# S11_LEDs.net
KiCad netlist of a schematic drawn in Altium Designer
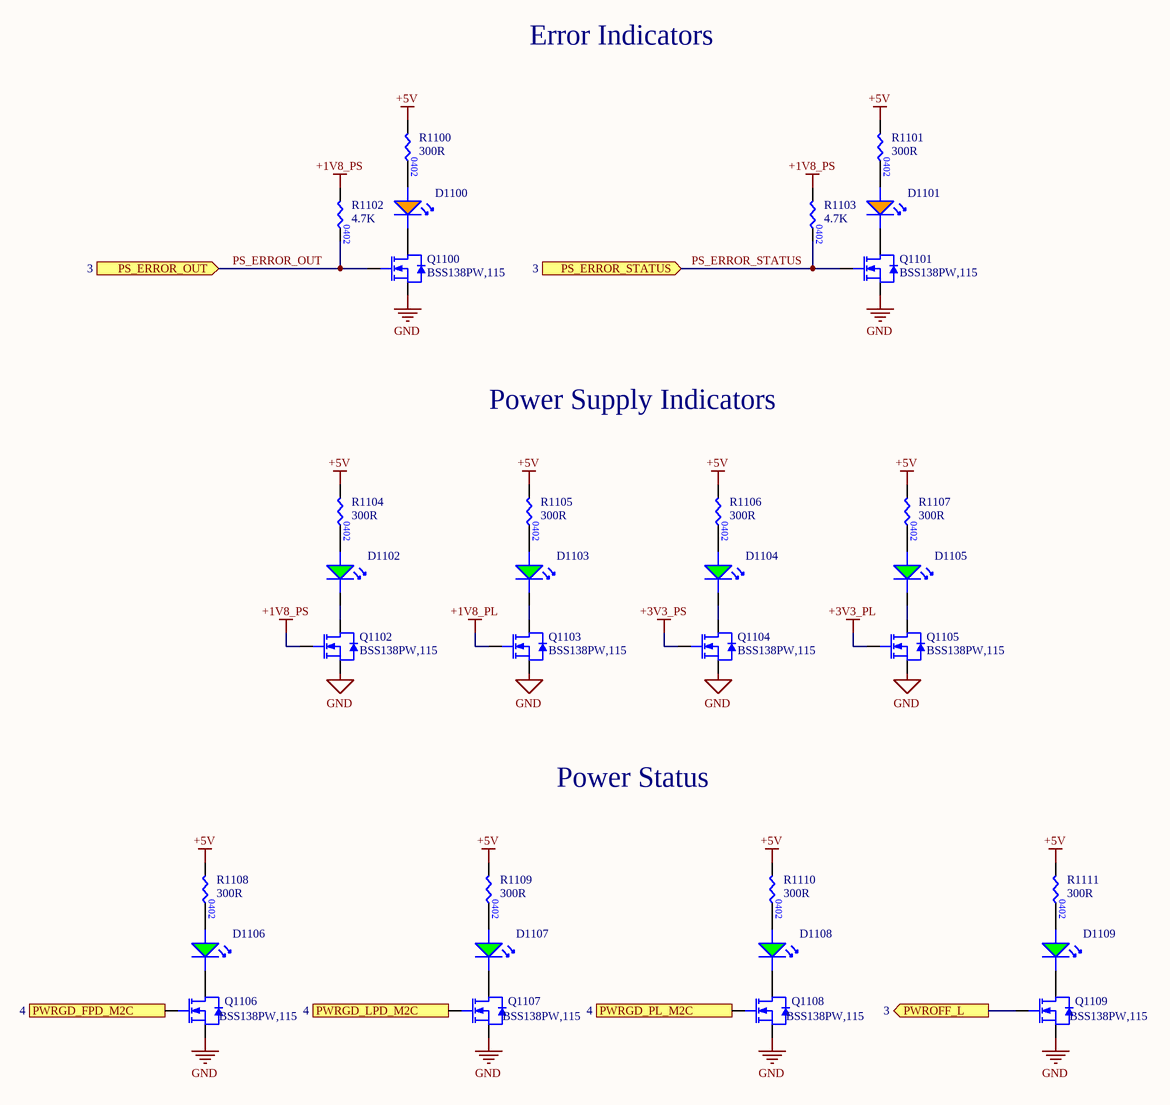
[diagram p0: S11_LEDs.SchDoc]

(export (version "E")
  (design (tool "Eeschema 10.0.6"))
  (components
    (comp (ref "D1100")
      (value "GENERIC LED - ORANGE")
      (footprint "LED_0603")
      (fields (field (name "MANUFACTURER PART NUMBER") "150060AS75000"))
      (libsource (lib "OpenCore_Sch_Lib") (part ".LED_ORANGE"))
    )
    (comp (ref "D1101")
      (value "GENERIC LED - ORANGE")
      (footprint "LED_0603")
      (fields (field (name "MANUFACTURER PART NUMBER") "150060AS75000"))
      (libsource (lib "OpenCore_Sch_Lib") (part ".LED_ORANGE"))
    )
    (comp (ref "D1102")
      (value "GENERIC LED - GREEN")
      (footprint "LED_0603")
      (fields (field (name "MANUFACTURER PART NUMBER") "150060VS75000"))
      (libsource (lib "OpenCore_Sch_Lib") (part ".LED_GREEN"))
    )
    (comp (ref "D1103")
      (value "GENERIC LED - GREEN")
      (footprint "LED_0603")
      (fields (field (name "MANUFACTURER PART NUMBER") "150060VS75000"))
      (libsource (lib "OpenCore_Sch_Lib") (part ".LED_GREEN"))
    )
    (comp (ref "D1104")
      (value "GENERIC LED - GREEN")
      (footprint "LED_0603")
      (fields (field (name "MANUFACTURER PART NUMBER") "150060VS75000"))
      (libsource (lib "OpenCore_Sch_Lib") (part ".LED_GREEN"))
    )
    (comp (ref "D1105")
      (value "GENERIC LED - GREEN")
      (footprint "LED_0603")
      (fields (field (name "MANUFACTURER PART NUMBER") "150060VS75000"))
      (libsource (lib "OpenCore_Sch_Lib") (part ".LED_GREEN"))
    )
    (comp (ref "D1106")
      (value "GENERIC LED - GREEN")
      (footprint "LED_0603")
      (fields (field (name "MANUFACTURER PART NUMBER") "150060VS75000"))
      (libsource (lib "OpenCore_Sch_Lib") (part ".LED_GREEN"))
    )
    (comp (ref "D1107")
      (value "GENERIC LED - GREEN")
      (footprint "LED_0603")
      (fields (field (name "MANUFACTURER PART NUMBER") "150060VS75000"))
      (libsource (lib "OpenCore_Sch_Lib") (part ".LED_GREEN"))
    )
    (comp (ref "D1108")
      (value "GENERIC LED - GREEN")
      (footprint "LED_0603")
      (fields (field (name "MANUFACTURER PART NUMBER") "150060VS75000"))
      (libsource (lib "OpenCore_Sch_Lib") (part ".LED_GREEN"))
    )
    (comp (ref "D1109")
      (value "GENERIC LED - GREEN")
      (footprint "LED_0603")
      (fields (field (name "MANUFACTURER PART NUMBER") "150060VS75000"))
      (libsource (lib "OpenCore_Sch_Lib") (part ".LED_GREEN"))
    )
    (comp (ref "Q1100")
      (value "BSS138PW,115")
      (footprint "NEXPERIA_SOT323")
      (description "MOSFET N-CH 60V 320MA SOT323")
      (libsource (lib "OpenCore_Sch_Lib") (part "BSS138PW,115"))
    )
    (comp (ref "Q1101")
      (value "BSS138PW,115")
      (footprint "NEXPERIA_SOT323")
      (description "MOSFET N-CH 60V 320MA SOT323")
      (libsource (lib "OpenCore_Sch_Lib") (part "BSS138PW,115"))
    )
    (comp (ref "Q1102")
      (value "BSS138PW,115")
      (footprint "NEXPERIA_SOT323")
      (description "MOSFET N-CH 60V 320MA SOT323")
      (libsource (lib "OpenCore_Sch_Lib") (part "BSS138PW,115"))
    )
    (comp (ref "Q1103")
      (value "BSS138PW,115")
      (footprint "NEXPERIA_SOT323")
      (description "MOSFET N-CH 60V 320MA SOT323")
      (libsource (lib "OpenCore_Sch_Lib") (part "BSS138PW,115"))
    )
    (comp (ref "Q1104")
      (value "BSS138PW,115")
      (footprint "NEXPERIA_SOT323")
      (description "MOSFET N-CH 60V 320MA SOT323")
      (libsource (lib "OpenCore_Sch_Lib") (part "BSS138PW,115"))
    )
    (comp (ref "Q1105")
      (value "BSS138PW,115")
      (footprint "NEXPERIA_SOT323")
      (description "MOSFET N-CH 60V 320MA SOT323")
      (libsource (lib "OpenCore_Sch_Lib") (part "BSS138PW,115"))
    )
    (comp (ref "Q1106")
      (value "BSS138PW,115")
      (footprint "NEXPERIA_SOT323")
      (description "MOSFET N-CH 60V 320MA SOT323")
      (libsource (lib "OpenCore_Sch_Lib") (part "BSS138PW,115"))
    )
    (comp (ref "Q1107")
      (value "BSS138PW,115")
      (footprint "NEXPERIA_SOT323")
      (description "MOSFET N-CH 60V 320MA SOT323")
      (libsource (lib "OpenCore_Sch_Lib") (part "BSS138PW,115"))
    )
    (comp (ref "Q1108")
      (value "BSS138PW,115")
      (footprint "NEXPERIA_SOT323")
      (description "MOSFET N-CH 60V 320MA SOT323")
      (libsource (lib "OpenCore_Sch_Lib") (part "BSS138PW,115"))
    )
    (comp (ref "Q1109")
      (value "BSS138PW,115")
      (footprint "NEXPERIA_SOT323")
      (description "MOSFET N-CH 60V 320MA SOT323")
      (libsource (lib "OpenCore_Sch_Lib") (part "BSS138PW,115"))
    )
    (comp (ref "R1100")
      (value "RES_0402")
      (footprint "RES0402")
      (description "RES 300 OHM 1% 1/16W 0402")
      (fields
        (field (name "MANUFACTURER") "YAGEO")
        (field (name "MANUFACTURER PART NUMBER") "RC0402FR-07300RL")
        (field (name "RESISTANCE") "300R")
      )
      (libsource (lib "OpenCore_Sch_Lib") (part ".RES_RC0402FR-07300RL"))
    )
    (comp (ref "R1101")
      (value "RES_0402")
      (footprint "RES0402")
      (description "RES 300 OHM 1% 1/16W 0402")
      (fields
        (field (name "MANUFACTURER") "YAGEO")
        (field (name "MANUFACTURER PART NUMBER") "RC0402FR-07300RL")
        (field (name "RESISTANCE") "300R")
      )
      (libsource (lib "OpenCore_Sch_Lib") (part ".RES_RC0402FR-07300RL"))
    )
    (comp (ref "R1102")
      (value "RES_0402")
      (footprint "RES0402")
      (description "RES 4.7K OHM 1% 1/16W 0402")
      (fields
        (field (name "MANUFACTURER") "YAGEO")
        (field (name "MANUFACTURER PART NUMBER") "RC0402FR-074K7L")
        (field (name "RESISTANCE") "4.7K")
      )
      (libsource (lib "OpenCore_Sch_Lib") (part ".RES_RC0402FR-074K7L"))
    )
    (comp (ref "R1103")
      (value "RES_0402")
      (footprint "RES0402")
      (description "RES 4.7K OHM 1% 1/16W 0402")
      (fields
        (field (name "MANUFACTURER") "YAGEO")
        (field (name "MANUFACTURER PART NUMBER") "RC0402FR-074K7L")
        (field (name "RESISTANCE") "4.7K")
      )
      (libsource (lib "OpenCore_Sch_Lib") (part ".RES_RC0402FR-074K7L"))
    )
    (comp (ref "R1104")
      (value "RES_0402")
      (footprint "RES0402")
      (description "RES 300 OHM 1% 1/16W 0402")
      (fields
        (field (name "MANUFACTURER") "YAGEO")
        (field (name "MANUFACTURER PART NUMBER") "RC0402FR-07300RL")
        (field (name "RESISTANCE") "300R")
      )
      (libsource (lib "OpenCore_Sch_Lib") (part ".RES_RC0402FR-07300RL"))
    )
    (comp (ref "R1105")
      (value "RES_0402")
      (footprint "RES0402")
      (description "RES 300 OHM 1% 1/16W 0402")
      (fields
        (field (name "MANUFACTURER") "YAGEO")
        (field (name "MANUFACTURER PART NUMBER") "RC0402FR-07300RL")
        (field (name "RESISTANCE") "300R")
      )
      (libsource (lib "OpenCore_Sch_Lib") (part ".RES_RC0402FR-07300RL"))
    )
    (comp (ref "R1106")
      (value "RES_0402")
      (footprint "RES0402")
      (description "RES 300 OHM 1% 1/16W 0402")
      (fields
        (field (name "MANUFACTURER") "YAGEO")
        (field (name "MANUFACTURER PART NUMBER") "RC0402FR-07300RL")
        (field (name "RESISTANCE") "300R")
      )
      (libsource (lib "OpenCore_Sch_Lib") (part ".RES_RC0402FR-07300RL"))
    )
    (comp (ref "R1107")
      (value "RES_0402")
      (footprint "RES0402")
      (description "RES 300 OHM 1% 1/16W 0402")
      (fields
        (field (name "MANUFACTURER") "YAGEO")
        (field (name "MANUFACTURER PART NUMBER") "RC0402FR-07300RL")
        (field (name "RESISTANCE") "300R")
      )
      (libsource (lib "OpenCore_Sch_Lib") (part ".RES_RC0402FR-07300RL"))
    )
    (comp (ref "R1108")
      (value "RES_0402")
      (footprint "RES0402")
      (description "RES 300 OHM 1% 1/16W 0402")
      (fields
        (field (name "MANUFACTURER") "YAGEO")
        (field (name "MANUFACTURER PART NUMBER") "RC0402FR-07300RL")
        (field (name "RESISTANCE") "300R")
      )
      (libsource (lib "OpenCore_Sch_Lib") (part ".RES_RC0402FR-07300RL"))
    )
    (comp (ref "R1109")
      (value "RES_0402")
      (footprint "RES0402")
      (description "RES 300 OHM 1% 1/16W 0402")
      (fields
        (field (name "MANUFACTURER") "YAGEO")
        (field (name "MANUFACTURER PART NUMBER") "RC0402FR-07300RL")
        (field (name "RESISTANCE") "300R")
      )
      (libsource (lib "OpenCore_Sch_Lib") (part ".RES_RC0402FR-07300RL"))
    )
    (comp (ref "R1110")
      (value "RES_0402")
      (footprint "RES0402")
      (description "RES 300 OHM 1% 1/16W 0402")
      (fields
        (field (name "MANUFACTURER") "YAGEO")
        (field (name "MANUFACTURER PART NUMBER") "RC0402FR-07300RL")
        (field (name "RESISTANCE") "300R")
      )
      (libsource (lib "OpenCore_Sch_Lib") (part ".RES_RC0402FR-07300RL"))
    )
    (comp (ref "R1111")
      (value "RES_0402")
      (footprint "RES0402")
      (description "RES 300 OHM 1% 1/16W 0402")
      (fields
        (field (name "MANUFACTURER") "YAGEO")
        (field (name "MANUFACTURER PART NUMBER") "RC0402FR-07300RL")
        (field (name "RESISTANCE") "300R")
      )
      (libsource (lib "OpenCore_Sch_Lib") (part ".RES_RC0402FR-07300RL"))
    )
  )
  (nets
    (net (code "1") (name "+1V8_PL") (class "Default")
      (node (ref "Q1103") (pin "1") (pinfunction "Gate_1") (pintype "passive"))
    )
    (net (code "2") (name "+1V8_PS") (class "Default")
      (node (ref "Q1102") (pin "1") (pinfunction "Gate_1") (pintype "passive"))
      (node (ref "R1102") (pin "1") (pinfunction "1_1") (pintype "passive"))
      (node (ref "R1103") (pin "1") (pinfunction "1_1") (pintype "passive"))
    )
    (net (code "3") (name "+3V3_PL") (class "Default")
      (node (ref "Q1105") (pin "1") (pinfunction "Gate_1") (pintype "passive"))
    )
    (net (code "4") (name "+3V3_PS") (class "Default")
      (node (ref "Q1104") (pin "1") (pinfunction "Gate_1") (pintype "passive"))
    )
    (net (code "5") (name "+5V") (class "Default")
      (node (ref "R1100") (pin "1") (pinfunction "1_1") (pintype "passive"))
      (node (ref "R1101") (pin "1") (pinfunction "1_1") (pintype "passive"))
      (node (ref "R1104") (pin "1") (pinfunction "1_1") (pintype "passive"))
      (node (ref "R1105") (pin "1") (pinfunction "1_1") (pintype "passive"))
      (node (ref "R1106") (pin "1") (pinfunction "1_1") (pintype "passive"))
      (node (ref "R1107") (pin "1") (pinfunction "1_1") (pintype "passive"))
      (node (ref "R1108") (pin "1") (pinfunction "1_1") (pintype "passive"))
      (node (ref "R1109") (pin "1") (pinfunction "1_1") (pintype "passive"))
      (node (ref "R1110") (pin "1") (pinfunction "1_1") (pintype "passive"))
      (node (ref "R1111") (pin "1") (pinfunction "1_1") (pintype "passive"))
    )
    (net (code "6") (name "/PS_ERROR_OUT") (class "Default")
      (node (ref "Q1100") (pin "1") (pinfunction "Gate_1") (pintype "passive"))
      (node (ref "R1102") (pin "2") (pinfunction "2_2") (pintype "passive"))
    )
    (net (code "7") (name "/PS_ERROR_STATUS") (class "Default")
      (node (ref "Q1101") (pin "1") (pinfunction "Gate_1") (pintype "passive"))
      (node (ref "R1103") (pin "2") (pinfunction "2_2") (pintype "passive"))
    )
    (net (code "8") (name "/PWRGD_FPD_M2C") (class "Default")
      (node (ref "Q1106") (pin "1") (pinfunction "Gate_1") (pintype "passive"))
    )
    (net (code "9") (name "/PWRGD_LPD_M2C") (class "Default")
      (node (ref "Q1107") (pin "1") (pinfunction "Gate_1") (pintype "passive"))
    )
    (net (code "10") (name "/PWRGD_PL_M2C") (class "Default")
      (node (ref "Q1108") (pin "1") (pinfunction "Gate_1") (pintype "passive"))
    )
    (net (code "11") (name "/PWROFF_L") (class "Default")
      (node (ref "Q1109") (pin "1") (pinfunction "Gate_1") (pintype "passive"))
    )
    (net (code "12") (name "GND") (class "Default")
      (node (ref "Q1100") (pin "2") (pinfunction "Source_2") (pintype "passive"))
      (node (ref "Q1101") (pin "2") (pinfunction "Source_2") (pintype "passive"))
      (node (ref "Q1102") (pin "2") (pinfunction "Source_2") (pintype "passive"))
      (node (ref "Q1103") (pin "2") (pinfunction "Source_2") (pintype "passive"))
      (node (ref "Q1104") (pin "2") (pinfunction "Source_2") (pintype "passive"))
      (node (ref "Q1105") (pin "2") (pinfunction "Source_2") (pintype "passive"))
      (node (ref "Q1106") (pin "2") (pinfunction "Source_2") (pintype "passive"))
      (node (ref "Q1107") (pin "2") (pinfunction "Source_2") (pintype "passive"))
      (node (ref "Q1108") (pin "2") (pinfunction "Source_2") (pintype "passive"))
      (node (ref "Q1109") (pin "2") (pinfunction "Source_2") (pintype "passive"))
    )
    (net (code "13") (name "Net-(D1100-Anode)") (class "Default")
      (node (ref "D1100") (pin "A") (pinfunction "Anode_A") (pintype "passive"))
      (node (ref "R1100") (pin "2") (pinfunction "2_2") (pintype "passive"))
    )
    (net (code "14") (name "Net-(D1100-Cathode)") (class "Default")
      (node (ref "D1100") (pin "K") (pinfunction "Cathode_K") (pintype "passive"))
      (node (ref "Q1100") (pin "3") (pinfunction "Drain_3") (pintype "passive"))
    )
    (net (code "15") (name "Net-(D1101-Anode)") (class "Default")
      (node (ref "D1101") (pin "A") (pinfunction "Anode_A") (pintype "passive"))
      (node (ref "R1101") (pin "2") (pinfunction "2_2") (pintype "passive"))
    )
    (net (code "16") (name "Net-(D1101-Cathode)") (class "Default")
      (node (ref "D1101") (pin "K") (pinfunction "Cathode_K") (pintype "passive"))
      (node (ref "Q1101") (pin "3") (pinfunction "Drain_3") (pintype "passive"))
    )
    (net (code "17") (name "Net-(D1102-Anode)") (class "Default")
      (node (ref "D1102") (pin "A") (pinfunction "Anode_A") (pintype "passive"))
      (node (ref "R1104") (pin "2") (pinfunction "2_2") (pintype "passive"))
    )
    (net (code "18") (name "Net-(D1102-Cathode)") (class "Default")
      (node (ref "D1102") (pin "K") (pinfunction "Cathode_K") (pintype "passive"))
      (node (ref "Q1102") (pin "3") (pinfunction "Drain_3") (pintype "passive"))
    )
    (net (code "19") (name "Net-(D1103-Anode)") (class "Default")
      (node (ref "D1103") (pin "A") (pinfunction "Anode_A") (pintype "passive"))
      (node (ref "R1105") (pin "2") (pinfunction "2_2") (pintype "passive"))
    )
    (net (code "20") (name "Net-(D1103-Cathode)") (class "Default")
      (node (ref "D1103") (pin "K") (pinfunction "Cathode_K") (pintype "passive"))
      (node (ref "Q1103") (pin "3") (pinfunction "Drain_3") (pintype "passive"))
    )
    (net (code "21") (name "Net-(D1104-Anode)") (class "Default")
      (node (ref "D1104") (pin "A") (pinfunction "Anode_A") (pintype "passive"))
      (node (ref "R1106") (pin "2") (pinfunction "2_2") (pintype "passive"))
    )
    (net (code "22") (name "Net-(D1104-Cathode)") (class "Default")
      (node (ref "D1104") (pin "K") (pinfunction "Cathode_K") (pintype "passive"))
      (node (ref "Q1104") (pin "3") (pinfunction "Drain_3") (pintype "passive"))
    )
    (net (code "23") (name "Net-(D1105-Anode)") (class "Default")
      (node (ref "D1105") (pin "A") (pinfunction "Anode_A") (pintype "passive"))
      (node (ref "R1107") (pin "2") (pinfunction "2_2") (pintype "passive"))
    )
    (net (code "24") (name "Net-(D1105-Cathode)") (class "Default")
      (node (ref "D1105") (pin "K") (pinfunction "Cathode_K") (pintype "passive"))
      (node (ref "Q1105") (pin "3") (pinfunction "Drain_3") (pintype "passive"))
    )
    (net (code "25") (name "Net-(D1106-Anode)") (class "Default")
      (node (ref "D1106") (pin "A") (pinfunction "Anode_A") (pintype "passive"))
      (node (ref "R1108") (pin "2") (pinfunction "2_2") (pintype "passive"))
    )
    (net (code "26") (name "Net-(D1106-Cathode)") (class "Default")
      (node (ref "D1106") (pin "K") (pinfunction "Cathode_K") (pintype "passive"))
      (node (ref "Q1106") (pin "3") (pinfunction "Drain_3") (pintype "passive"))
    )
    (net (code "27") (name "Net-(D1107-Anode)") (class "Default")
      (node (ref "D1107") (pin "A") (pinfunction "Anode_A") (pintype "passive"))
      (node (ref "R1109") (pin "2") (pinfunction "2_2") (pintype "passive"))
    )
    (net (code "28") (name "Net-(D1107-Cathode)") (class "Default")
      (node (ref "D1107") (pin "K") (pinfunction "Cathode_K") (pintype "passive"))
      (node (ref "Q1107") (pin "3") (pinfunction "Drain_3") (pintype "passive"))
    )
    (net (code "29") (name "Net-(D1108-Anode)") (class "Default")
      (node (ref "D1108") (pin "A") (pinfunction "Anode_A") (pintype "passive"))
      (node (ref "R1110") (pin "2") (pinfunction "2_2") (pintype "passive"))
    )
    (net (code "30") (name "Net-(D1108-Cathode)") (class "Default")
      (node (ref "D1108") (pin "K") (pinfunction "Cathode_K") (pintype "passive"))
      (node (ref "Q1108") (pin "3") (pinfunction "Drain_3") (pintype "passive"))
    )
    (net (code "31") (name "Net-(D1109-Anode)") (class "Default")
      (node (ref "D1109") (pin "A") (pinfunction "Anode_A") (pintype "passive"))
      (node (ref "R1111") (pin "2") (pinfunction "2_2") (pintype "passive"))
    )
    (net (code "32") (name "Net-(D1109-Cathode)") (class "Default")
      (node (ref "D1109") (pin "K") (pinfunction "Cathode_K") (pintype "passive"))
      (node (ref "Q1109") (pin "3") (pinfunction "Drain_3") (pintype "passive"))
    )
  )
)
